# board_volt_sense.net
KiCad netlist of a schematic drawn in Altium Designer
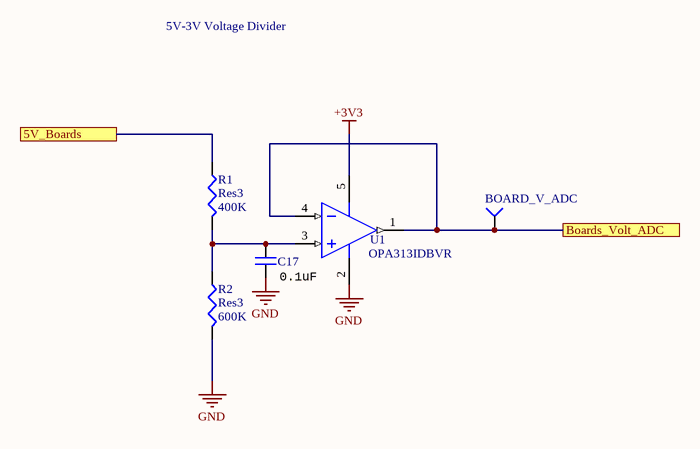
[diagram p0: board_volt_sense.SchDoc]

(export (version "E")
  (design (tool "Eeschema 10.0.6"))
  (components
    (comp (ref "BOARD_V_ADC")
      (value "BOARD_V_ADC")
      (footprint "TESTPOINT")
      (description "TESTPOINT_SMD")
      (libsource (lib "UWRT_Schematic_Library_2020") (part "TESTPOINT_SMD"))
    )
    (comp (ref "C17")
      (value "0.1uF")
      (footprint "CAPC0603(1608)55_N")
      (description "CAP CER 0.1UF 16V X7R 0603")
      (fields (field (name "MPN") "CC0603KRX7R7BB104") (field (name "MANUFACTURER") "Yageo"))
      (libsource (lib "*") (part "CAP_0.1uF_16V_0603"))
    )
    (comp (ref "R1")
      (value "Res3")
      (footprint "J1-0603")
      (description "Resistor")
      (fields (field (name "ALTIUM_VALUE") "400K") (field (name "PUBLISHER") "Altium Limited"))
      (libsource (lib "Miscellaneous Devices") (part "Res3"))
    )
    (comp (ref "R2")
      (value "Res3")
      (footprint "J1-0603")
      (description "Resistor")
      (fields (field (name "ALTIUM_VALUE") "600K") (field (name "PUBLISHER") "Altium Limited"))
      (libsource (lib "Miscellaneous Devices") (part "Res3"))
    )
    (comp (ref "U1")
      (value "OPA313IDBVR")
      (footprint "DBV0005A_M")
      (fields
        (field (name "MANUFACTURER") "Texas Instruments")
        (field (name "DIGI-KEY PART NUMBER") "296-35607-1-ND")
      )
      (libsource (lib "UWRT_Schematic_Library_2020") (part "OPAMP"))
    )
  )
  (nets
    (net (code "1") (name "+3V3") (class "Default")
      (node (ref "U1") (pin "5") (pinfunction "V+_5") (pintype "power_in"))
    )
    (net (code "2") (name "/5V_Boards") (class "Default")
      (node (ref "R1") (pin "1") (pinfunction "1_1") (pintype "passive"))
    )
    (net (code "3") (name "/Boards_Volt_ADC") (class "Default")
      (node (ref "BOARD_V_ADC") (pin "1") (pinfunction "=value_1") (pintype "passive"))
      (node (ref "U1") (pin "1") (pinfunction "OUT_1") (pintype "output"))
      (node (ref "U1") (pin "4") (pinfunction "IN-_4") (pintype "input"))
    )
    (net (code "4") (name "GND") (class "Default")
      (node (ref "C17") (pin "1") (pinfunction "1_1") (pintype "passive"))
      (node (ref "R2") (pin "2") (pinfunction "2_2") (pintype "passive"))
      (node (ref "U1") (pin "2") (pinfunction "V-_2") (pintype "power_in"))
    )
    (net (code "5") (name "Net-(U1-IN+)") (class "Default")
      (node (ref "C17") (pin "2") (pinfunction "2_2") (pintype "passive"))
      (node (ref "R1") (pin "2") (pinfunction "2_2") (pintype "passive"))
      (node (ref "R2") (pin "1") (pinfunction "1_1") (pintype "passive"))
      (node (ref "U1") (pin "3") (pinfunction "IN+_3") (pintype "input"))
    )
  )
)
